# sensor2.net
KiCad netlist of a schematic drawn in EAGLE
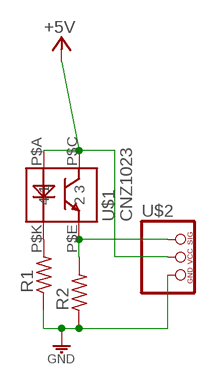
[diagram p0: schematic, sheet 1]

(export (version "E")
  (design (tool "Eeschema 10.0.6"))
  (components
    (comp (ref "R1")
      (value "RESISTORS")
      (footprint "eagle-import:R_3216")
      (libsource (lib "eagle-import") (part "RESISTORS"))
    )
    (comp (ref "R2")
      (value "RESISTORS")
      (footprint "eagle-import:R_3216")
      (libsource (lib "eagle-import") (part "RESISTORS"))
    )
    (comp (ref "U$1")
      (value "CNZ1023")
      (footprint "eagle-import:CNZ1023")
      (libsource (lib "eagle-import") (part "CNZ1023"))
    )
    (comp (ref "U$2")
      (value "PINHD-SENSOR")
      (footprint "eagle-import:1_03(KIKAKU)")
      (libsource (lib "eagle-import") (part "PINHD-SENSOR"))
    )
  )
  (nets
    (net (code "1") (name "+5V") (class "Default")
      (node (ref "U$1") (pin "P$A") (pinfunction "1_P$A") (pintype "output"))
      (node (ref "U$1") (pin "P$C") (pinfunction "3_P$C") (pintype "input"))
      (node (ref "U$2") (pin "VCC") (pinfunction "VCC_VCC") (pintype "passive"))
    )
    (net (code "2") (name "GND") (class "Default")
      (node (ref "R1") (pin "1") (pinfunction "1_1") (pintype "passive"))
      (node (ref "R2") (pin "1") (pinfunction "1_1") (pintype "passive"))
      (node (ref "U$2") (pin "GND") (pinfunction "GND_GND") (pintype "passive"))
    )
    (net (code "3") (name "Net-(U$1-2)") (class "Default")
      (node (ref "R2") (pin "2") (pinfunction "2_2") (pintype "passive"))
      (node (ref "U$1") (pin "P$E") (pinfunction "2_P$E") (pintype "output"))
      (node (ref "U$2") (pin "SIG") (pinfunction "SIG_SIG") (pintype "passive"))
    )
    (net (code "4") (name "Net-(U$1-4)") (class "Default")
      (node (ref "R1") (pin "2") (pinfunction "2_2") (pintype "passive"))
      (node (ref "U$1") (pin "P$K") (pinfunction "4_P$K") (pintype "input"))
    )
  )
)
